# MotorEncoders.net
KiCad netlist of a schematic drawn in Altium Designer
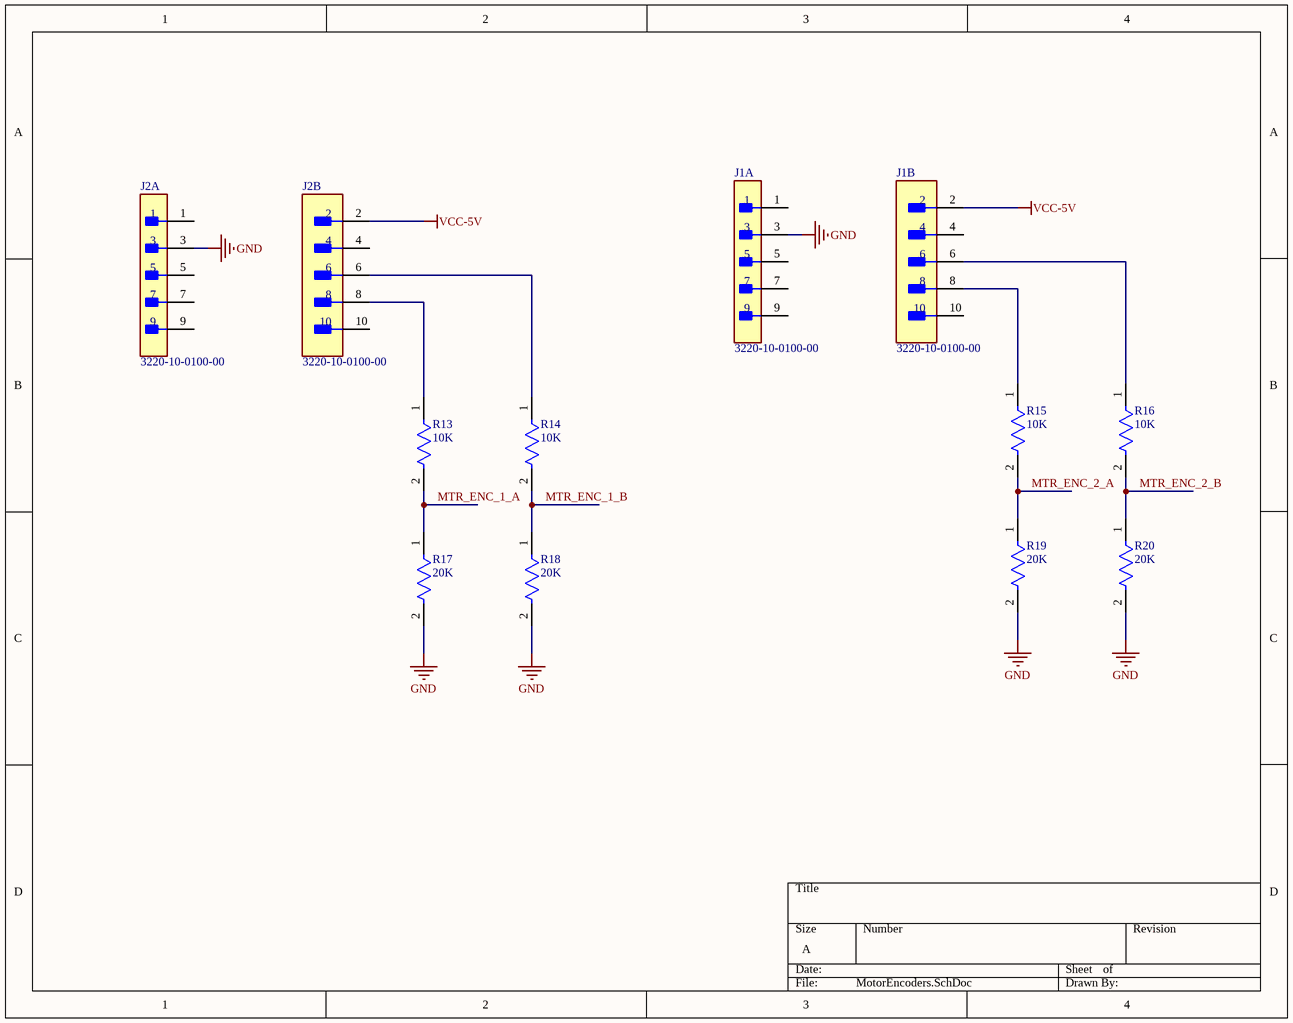
[diagram p0: MotorEncoders.SchDoc]

(export (version "E")
  (design (tool "Eeschema 10.0.6"))
  (components
    (comp (ref "J1")
      (value "3220-10-0100-00")
      (footprint "FP-3220-10-0100-00-MFG")
      (description "3220-10-0100-00 Conn Shrouded Header (4 Sides) HDR 10 POS 1.27mm Solder ST Top Entry Thru-Hole")
      (libsource (lib "Altium Content Vault") (part "14c31cd5c0c2cdb8462fce9a03c7dcb"))
    )
    (comp (ref "J2")
      (value "3220-10-0100-00")
      (footprint "FP-3220-10-0100-00-MFG")
      (description "3220-10-0100-00 Conn Shrouded Header (4 Sides) HDR 10 POS 1.27mm Solder ST Top Entry Thru-Hole")
      (libsource (lib "Altium Content Vault") (part "14c31cd5c0c2cdb8462fce9a03c7dcb"))
    )
    (comp (ref "R13")
      (value "10K")
      (footprint "FP-RC0603-0_55-IPC_C")
      (description "RES 10K OHM 1% 1/10W 0603")
      (fields (field (name "TOLERANCE") "1%"))
      (libsource (lib "Altium Content Vault") (part "1029c3af85768c4190bb7ad29bc67b5"))
    )
    (comp (ref "R14")
      (value "10K")
      (footprint "FP-RC0603-0_55-IPC_C")
      (description "RES 10K OHM 1% 1/10W 0603")
      (fields (field (name "TOLERANCE") "1%"))
      (libsource (lib "Altium Content Vault") (part "1029c3af85768c4190bb7ad29bc67b5"))
    )
    (comp (ref "R15")
      (value "10K")
      (footprint "FP-RC0603-0_55-IPC_C")
      (description "RES 10K OHM 1% 1/10W 0603")
      (fields (field (name "TOLERANCE") "1%"))
      (libsource (lib "Altium Content Vault") (part "1029c3af85768c4190bb7ad29bc67b5"))
    )
    (comp (ref "R16")
      (value "10K")
      (footprint "FP-RC0603-0_55-IPC_C")
      (description "RES 10K OHM 1% 1/10W 0603")
      (fields (field (name "TOLERANCE") "1%"))
      (libsource (lib "Altium Content Vault") (part "1029c3af85768c4190bb7ad29bc67b5"))
    )
    (comp (ref "R17")
      (value "20K")
      (footprint "FP-RC0603-0_55-IPC_C")
      (description "RES 20K OHM 1% 1/10W 0603")
      (fields (field (name "TOLERANCE") "1%"))
      (libsource (lib "Altium Content Vault") (part "1029c3af85768c4190bb7ad29bc67b5"))
    )
    (comp (ref "R18")
      (value "20K")
      (footprint "FP-RC0603-0_55-IPC_C")
      (description "RES 20K OHM 1% 1/10W 0603")
      (fields (field (name "TOLERANCE") "1%"))
      (libsource (lib "Altium Content Vault") (part "1029c3af85768c4190bb7ad29bc67b5"))
    )
    (comp (ref "R19")
      (value "20K")
      (footprint "FP-RC0603-0_55-IPC_C")
      (description "RES 20K OHM 1% 1/10W 0603")
      (fields (field (name "TOLERANCE") "1%"))
      (libsource (lib "Altium Content Vault") (part "1029c3af85768c4190bb7ad29bc67b5"))
    )
    (comp (ref "R20")
      (value "20K")
      (footprint "FP-RC0603-0_55-IPC_C")
      (description "RES 20K OHM 1% 1/10W 0603")
      (fields (field (name "TOLERANCE") "1%"))
      (libsource (lib "Altium Content Vault") (part "1029c3af85768c4190bb7ad29bc67b5"))
    )
  )
  (nets
    (net (code "1") (name "/MTR_ENC_1_A") (class "Default")
      (node (ref "R13") (pin "2") (pinfunction "2_2") (pintype "passive"))
      (node (ref "R17") (pin "1") (pinfunction "1_1") (pintype "passive"))
    )
    (net (code "2") (name "/MTR_ENC_1_B") (class "Default")
      (node (ref "R14") (pin "2") (pinfunction "2_2") (pintype "passive"))
      (node (ref "R18") (pin "1") (pinfunction "1_1") (pintype "passive"))
    )
    (net (code "3") (name "/MTR_ENC_2_A") (class "Default")
      (node (ref "R15") (pin "2") (pinfunction "2_2") (pintype "passive"))
      (node (ref "R19") (pin "1") (pinfunction "1_1") (pintype "passive"))
    )
    (net (code "4") (name "/MTR_ENC_2_B") (class "Default")
      (node (ref "R16") (pin "2") (pinfunction "2_2") (pintype "passive"))
      (node (ref "R20") (pin "1") (pinfunction "1_1") (pintype "passive"))
    )
    (net (code "5") (name "GND") (class "Default")
      (node (ref "J1") (pin "3") (pinfunction "3_3") (pintype "passive"))
      (node (ref "J2") (pin "3") (pinfunction "3_3") (pintype "passive"))
      (node (ref "R17") (pin "2") (pinfunction "2_2") (pintype "passive"))
      (node (ref "R18") (pin "2") (pinfunction "2_2") (pintype "passive"))
      (node (ref "R19") (pin "2") (pinfunction "2_2") (pintype "passive"))
      (node (ref "R20") (pin "2") (pinfunction "2_2") (pintype "passive"))
    )
    (net (code "6") (name "Net-(J1-Pad6)") (class "Default")
      (node (ref "J1") (pin "6") (pinfunction "6_6") (pintype "passive"))
      (node (ref "R16") (pin "1") (pinfunction "1_1") (pintype "passive"))
    )
    (net (code "7") (name "Net-(J1-Pad8)") (class "Default")
      (node (ref "J1") (pin "8") (pinfunction "8_8") (pintype "passive"))
      (node (ref "R15") (pin "1") (pinfunction "1_1") (pintype "passive"))
    )
    (net (code "8") (name "Net-(J2-Pad6)") (class "Default")
      (node (ref "J2") (pin "6") (pinfunction "6_6") (pintype "passive"))
      (node (ref "R14") (pin "1") (pinfunction "1_1") (pintype "passive"))
    )
    (net (code "9") (name "Net-(J2-Pad8)") (class "Default")
      (node (ref "J2") (pin "8") (pinfunction "8_8") (pintype "passive"))
      (node (ref "R13") (pin "1") (pinfunction "1_1") (pintype "passive"))
    )
    (net (code "10") (name "VCC-5V") (class "Default")
      (node (ref "J1") (pin "2") (pinfunction "2_2") (pintype "passive"))
      (node (ref "J2") (pin "2") (pinfunction "2_2") (pintype "passive"))
    )
    (net (code "11") (name "unconnected-(J1-Pad1)") (class "Default")
      (node (ref "J1") (pin "1") (pinfunction "1_1") (pintype "passive"))
    )
    (net (code "12") (name "unconnected-(J1-Pad4)") (class "Default")
      (node (ref "J1") (pin "4") (pinfunction "4_4") (pintype "passive"))
    )
    (net (code "13") (name "unconnected-(J1-Pad5)") (class "Default")
      (node (ref "J1") (pin "5") (pinfunction "5_5") (pintype "passive"))
    )
    (net (code "14") (name "unconnected-(J1-Pad7)") (class "Default")
      (node (ref "J1") (pin "7") (pinfunction "7_7") (pintype "passive"))
    )
    (net (code "15") (name "unconnected-(J1-Pad9)") (class "Default")
      (node (ref "J1") (pin "9") (pinfunction "9_9") (pintype "passive"))
    )
    (net (code "16") (name "unconnected-(J1-Pad10)") (class "Default")
      (node (ref "J1") (pin "10") (pinfunction "10_10") (pintype "passive"))
    )
    (net (code "17") (name "unconnected-(J2-Pad1)") (class "Default")
      (node (ref "J2") (pin "1") (pinfunction "1_1") (pintype "passive"))
    )
    (net (code "18") (name "unconnected-(J2-Pad4)") (class "Default")
      (node (ref "J2") (pin "4") (pinfunction "4_4") (pintype "passive"))
    )
    (net (code "19") (name "unconnected-(J2-Pad5)") (class "Default")
      (node (ref "J2") (pin "5") (pinfunction "5_5") (pintype "passive"))
    )
    (net (code "20") (name "unconnected-(J2-Pad7)") (class "Default")
      (node (ref "J2") (pin "7") (pinfunction "7_7") (pintype "passive"))
    )
    (net (code "21") (name "unconnected-(J2-Pad9)") (class "Default")
      (node (ref "J2") (pin "9") (pinfunction "9_9") (pintype "passive"))
    )
    (net (code "22") (name "unconnected-(J2-Pad10)") (class "Default")
      (node (ref "J2") (pin "10") (pinfunction "10_10") (pintype "passive"))
    )
  )
)
